# Light_Module.net
KiCad netlist of a schematic drawn in EAGLE
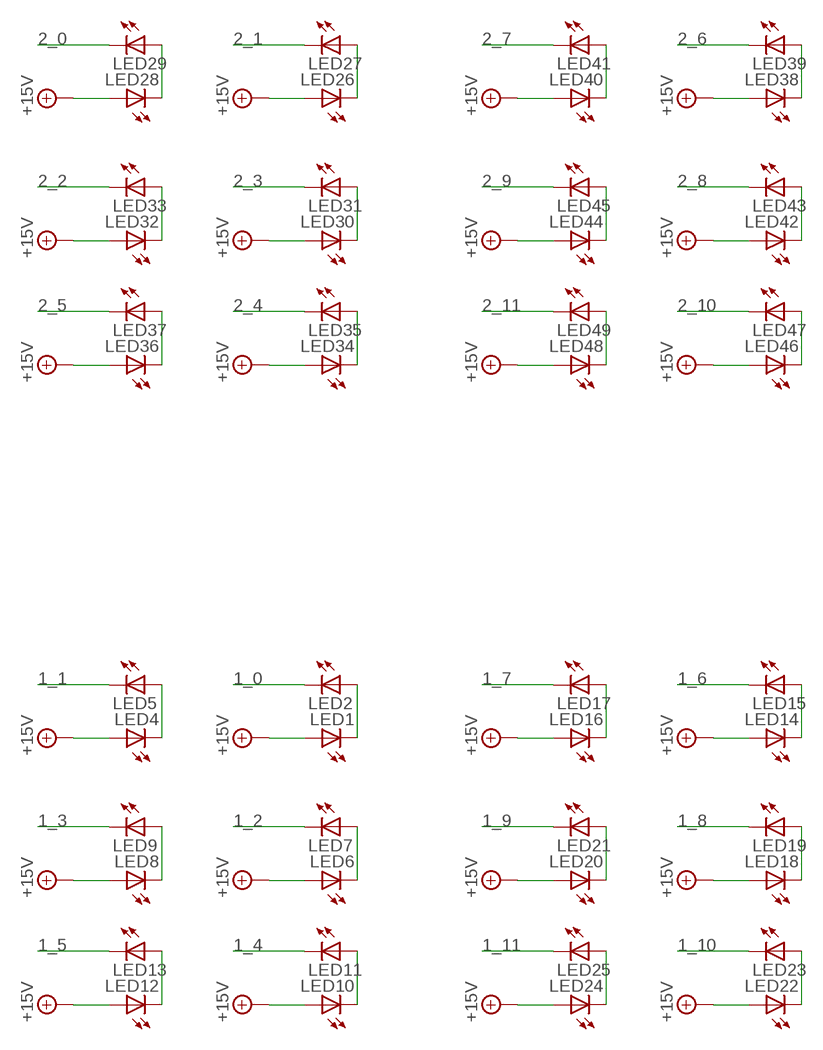
[diagram p0: schematic, sheet 1]
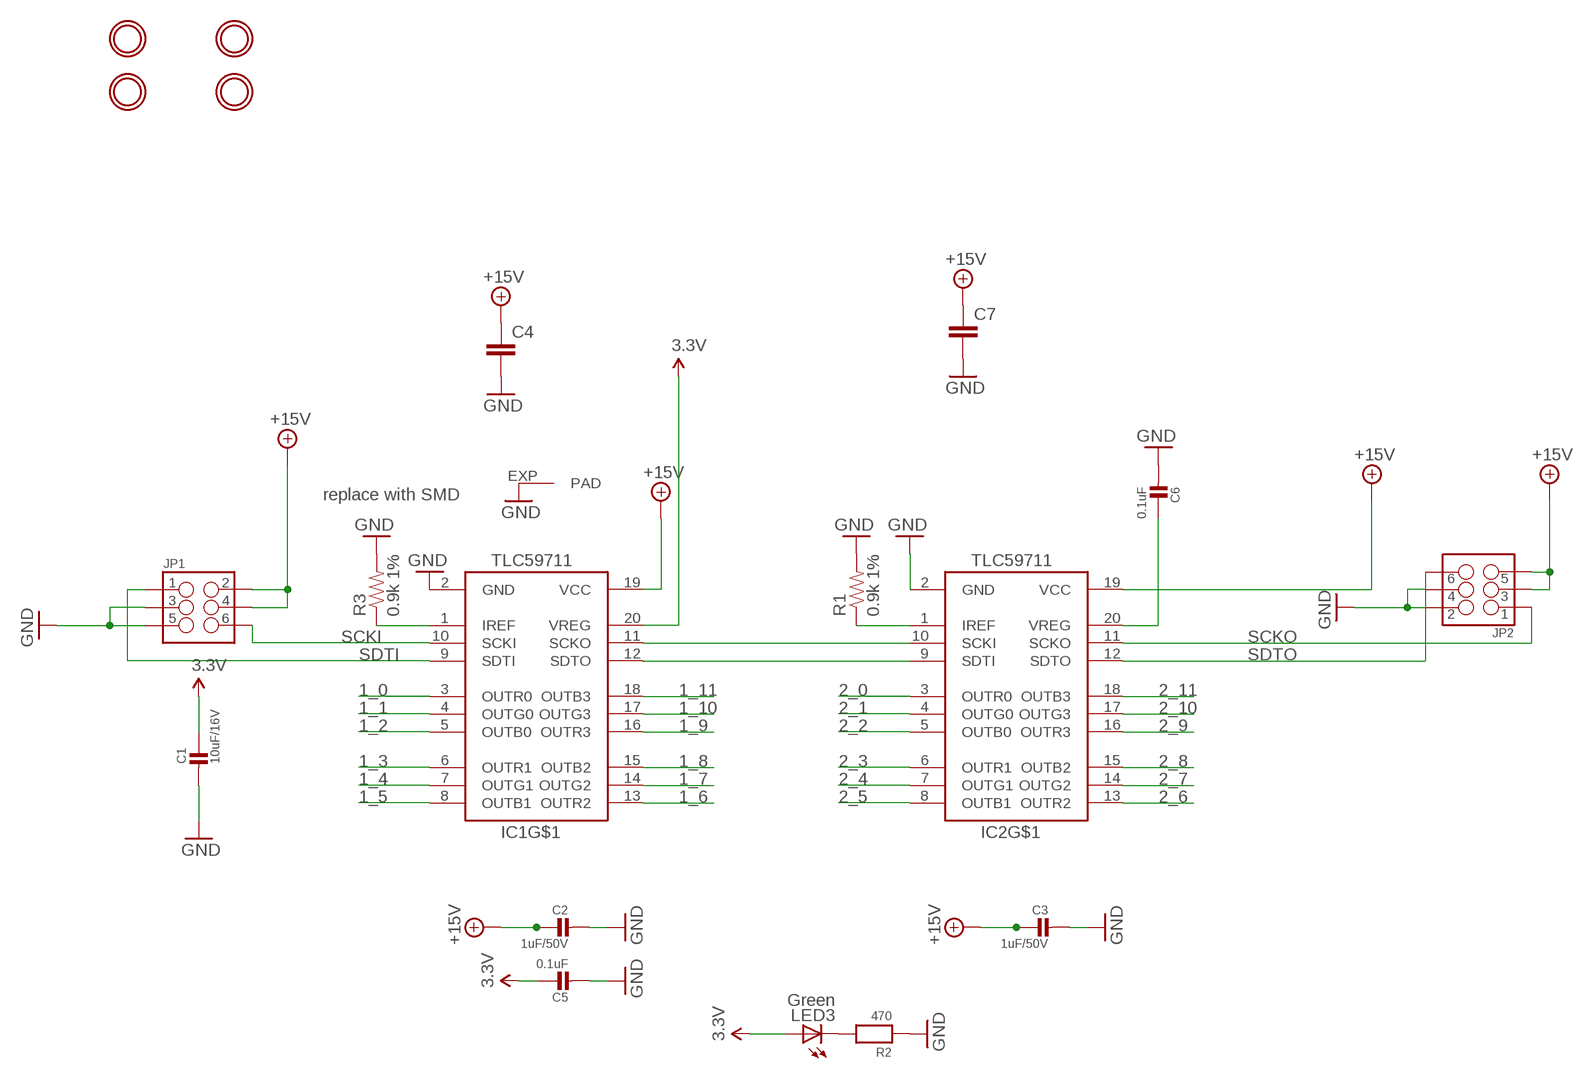
[diagram p1: schematic, sheet 2]

(export (version "E")
  (design (tool "Eeschema 10.0.6"))
  (components
    (comp (ref "LED1")
      (value "LED")
      (footprint "eagle-import:DS205")
      (libsource (lib "eagle-import") (part "digikey_LED"))
    )
    (comp (ref "LED2")
      (value "LED")
      (footprint "eagle-import:DS205")
      (libsource (lib "eagle-import") (part "digikey_LED"))
    )
    (comp (ref "LED4")
      (value "LED")
      (footprint "eagle-import:DS205")
      (libsource (lib "eagle-import") (part "digikey_LED"))
    )
    (comp (ref "LED5")
      (value "LED")
      (footprint "eagle-import:DS205")
      (libsource (lib "eagle-import") (part "digikey_LED"))
    )
    (comp (ref "LED6")
      (value "LED")
      (footprint "eagle-import:DS205")
      (libsource (lib "eagle-import") (part "digikey_LED"))
    )
    (comp (ref "LED7")
      (value "LED")
      (footprint "eagle-import:DS205")
      (libsource (lib "eagle-import") (part "digikey_LED"))
    )
    (comp (ref "LED8")
      (value "LED")
      (footprint "eagle-import:DS205")
      (libsource (lib "eagle-import") (part "digikey_LED"))
    )
    (comp (ref "LED9")
      (value "LED")
      (footprint "eagle-import:DS205")
      (libsource (lib "eagle-import") (part "digikey_LED"))
    )
    (comp (ref "LED10")
      (value "LED")
      (footprint "eagle-import:DS205")
      (libsource (lib "eagle-import") (part "digikey_LED"))
    )
    (comp (ref "LED11")
      (value "LED")
      (footprint "eagle-import:DS205")
      (libsource (lib "eagle-import") (part "digikey_LED"))
    )
    (comp (ref "LED12")
      (value "LED")
      (footprint "eagle-import:DS205")
      (libsource (lib "eagle-import") (part "digikey_LED"))
    )
    (comp (ref "LED13")
      (value "LED")
      (footprint "eagle-import:DS205")
      (libsource (lib "eagle-import") (part "digikey_LED"))
    )
    (comp (ref "LED14")
      (value "LED")
      (footprint "eagle-import:DS205")
      (libsource (lib "eagle-import") (part "digikey_LED"))
    )
    (comp (ref "LED15")
      (value "LED")
      (footprint "eagle-import:DS205")
      (libsource (lib "eagle-import") (part "digikey_LED"))
    )
    (comp (ref "LED16")
      (value "LED")
      (footprint "eagle-import:DS205")
      (libsource (lib "eagle-import") (part "digikey_LED"))
    )
    (comp (ref "LED17")
      (value "LED")
      (footprint "eagle-import:DS205")
      (libsource (lib "eagle-import") (part "digikey_LED"))
    )
    (comp (ref "LED18")
      (value "LED")
      (footprint "eagle-import:DS205")
      (libsource (lib "eagle-import") (part "digikey_LED"))
    )
    (comp (ref "LED19")
      (value "LED")
      (footprint "eagle-import:DS205")
      (libsource (lib "eagle-import") (part "digikey_LED"))
    )
    (comp (ref "LED20")
      (value "LED")
      (footprint "eagle-import:DS205")
      (libsource (lib "eagle-import") (part "digikey_LED"))
    )
    (comp (ref "LED21")
      (value "LED")
      (footprint "eagle-import:DS205")
      (libsource (lib "eagle-import") (part "digikey_LED"))
    )
    (comp (ref "LED22")
      (value "LED")
      (footprint "eagle-import:DS205")
      (libsource (lib "eagle-import") (part "digikey_LED"))
    )
    (comp (ref "LED23")
      (value "LED")
      (footprint "eagle-import:DS205")
      (libsource (lib "eagle-import") (part "digikey_LED"))
    )
    (comp (ref "LED24")
      (value "LED")
      (footprint "eagle-import:DS205")
      (libsource (lib "eagle-import") (part "digikey_LED"))
    )
    (comp (ref "LED25")
      (value "LED")
      (footprint "eagle-import:DS205")
      (libsource (lib "eagle-import") (part "digikey_LED"))
    )
    (comp (ref "LED26")
      (value "LED")
      (footprint "eagle-import:DS205")
      (libsource (lib "eagle-import") (part "digikey_LED"))
    )
    (comp (ref "LED27")
      (value "LED")
      (footprint "eagle-import:DS205")
      (libsource (lib "eagle-import") (part "digikey_LED"))
    )
    (comp (ref "LED28")
      (value "LED")
      (footprint "eagle-import:DS205")
      (libsource (lib "eagle-import") (part "digikey_LED"))
    )
    (comp (ref "LED29")
      (value "LED")
      (footprint "eagle-import:DS205")
      (libsource (lib "eagle-import") (part "digikey_LED"))
    )
    (comp (ref "LED30")
      (value "LED")
      (footprint "eagle-import:DS205")
      (libsource (lib "eagle-import") (part "digikey_LED"))
    )
    (comp (ref "LED31")
      (value "LED")
      (footprint "eagle-import:DS205")
      (libsource (lib "eagle-import") (part "digikey_LED"))
    )
    (comp (ref "LED32")
      (value "LED")
      (footprint "eagle-import:DS205")
      (libsource (lib "eagle-import") (part "digikey_LED"))
    )
    (comp (ref "LED33")
      (value "LED")
      (footprint "eagle-import:DS205")
      (libsource (lib "eagle-import") (part "digikey_LED"))
    )
    (comp (ref "LED34")
      (value "LED")
      (footprint "eagle-import:DS205")
      (libsource (lib "eagle-import") (part "digikey_LED"))
    )
    (comp (ref "LED35")
      (value "LED")
      (footprint "eagle-import:DS205")
      (libsource (lib "eagle-import") (part "digikey_LED"))
    )
    (comp (ref "LED36")
      (value "LED")
      (footprint "eagle-import:DS205")
      (libsource (lib "eagle-import") (part "digikey_LED"))
    )
    (comp (ref "LED37")
      (value "LED")
      (footprint "eagle-import:DS205")
      (libsource (lib "eagle-import") (part "digikey_LED"))
    )
    (comp (ref "LED38")
      (value "LED")
      (footprint "eagle-import:DS205")
      (libsource (lib "eagle-import") (part "digikey_LED"))
    )
    (comp (ref "LED39")
      (value "LED")
      (footprint "eagle-import:DS205")
      (libsource (lib "eagle-import") (part "digikey_LED"))
    )
    (comp (ref "LED40")
      (value "LED")
      (footprint "eagle-import:DS205")
      (libsource (lib "eagle-import") (part "digikey_LED"))
    )
    (comp (ref "LED41")
      (value "LED")
      (footprint "eagle-import:DS205")
      (libsource (lib "eagle-import") (part "digikey_LED"))
    )
    (comp (ref "LED42")
      (value "LED")
      (footprint "eagle-import:DS205")
      (libsource (lib "eagle-import") (part "digikey_LED"))
    )
    (comp (ref "LED43")
      (value "LED")
      (footprint "eagle-import:DS205")
      (libsource (lib "eagle-import") (part "digikey_LED"))
    )
    (comp (ref "LED44")
      (value "LED")
      (footprint "eagle-import:DS205")
      (libsource (lib "eagle-import") (part "digikey_LED"))
    )
    (comp (ref "LED45")
      (value "LED")
      (footprint "eagle-import:DS205")
      (libsource (lib "eagle-import") (part "digikey_LED"))
    )
    (comp (ref "LED46")
      (value "LED")
      (footprint "eagle-import:DS205")
      (libsource (lib "eagle-import") (part "digikey_LED"))
    )
    (comp (ref "LED47")
      (value "LED")
      (footprint "eagle-import:DS205")
      (libsource (lib "eagle-import") (part "digikey_LED"))
    )
    (comp (ref "LED48")
      (value "LED")
      (footprint "eagle-import:DS205")
      (libsource (lib "eagle-import") (part "digikey_LED"))
    )
    (comp (ref "LED49")
      (value "LED")
      (footprint "eagle-import:DS205")
      (libsource (lib "eagle-import") (part "digikey_LED"))
    )
    (comp (ref "C1")
      (value "10uF/16V")
      (footprint "eagle-import:0805")
      (libsource (lib "eagle-import") (part "CAP_CERAMIC0805"))
    )
    (comp (ref "C2")
      (value "1uF/50V")
      (footprint "eagle-import:0805")
      (libsource (lib "eagle-import") (part "CAP_CERAMIC0805"))
    )
    (comp (ref "C3")
      (value "1uF/50V")
      (footprint "eagle-import:0805")
      (libsource (lib "eagle-import") (part "CAP_CERAMIC0805"))
    )
    (comp (ref "C4")
      (value "CAP1206")
      (footprint "eagle-import:1206")
      (libsource (lib "eagle-import") (part "CAP1206"))
    )
    (comp (ref "C5")
      (value "0.1uF")
      (footprint "eagle-import:0805")
      (libsource (lib "eagle-import") (part "CAP_CERAMIC0805"))
    )
    (comp (ref "C6")
      (value "0.1uF")
      (footprint "eagle-import:0805")
      (libsource (lib "eagle-import") (part "CAP_CERAMIC0805"))
    )
    (comp (ref "C7")
      (value "CAP_")
      (footprint "eagle-import:AXIAL-5MM")
      (libsource (lib "eagle-import") (part "CAP_"))
    )
    (comp (ref "IC1")
      (value "TLC59711")
      (footprint "eagle-import:HTSSOP20DAP")
      (libsource (lib "eagle-import") (part "TLC59711"))
    )
    (comp (ref "IC2")
      (value "TLC59711")
      (footprint "eagle-import:HTSSOP20DAP")
      (libsource (lib "eagle-import") (part "TLC59711"))
    )
    (comp (ref "JP1")
      (value "M03X2FEMALE_SMD")
      (footprint "eagle-import:2X3_SMD")
      (libsource (lib "eagle-import") (part "M03X2FEMALE_SMD"))
    )
    (comp (ref "JP2")
      (value "M03X2FEMALE_SMD")
      (footprint "eagle-import:2X3_SMD")
      (libsource (lib "eagle-import") (part "M03X2FEMALE_SMD"))
    )
    (comp (ref "LED3")
      (value "Green")
      (footprint "eagle-import:CHIP-LED0805")
      (libsource (lib "eagle-import") (part "LEDCHIP-LED0805"))
    )
    (comp (ref "R1")
      (value "0.9k 1%")
      (footprint "eagle-import:1206")
      (libsource (lib "eagle-import") (part "RESISTOR1206"))
    )
    (comp (ref "R2")
      (value "470")
      (footprint "eagle-import:0805")
      (libsource (lib "eagle-import") (part "RESISTOR0805"))
    )
    (comp (ref "R3")
      (value "0.9k 1%")
      (footprint "eagle-import:1206")
      (libsource (lib "eagle-import") (part "RESISTOR1206"))
    )
    (comp (ref "U$1")
      (value "MOUNTINGHOLE2.5")
      (footprint "eagle-import:MOUNTINGHOLE_2.5_PLATED")
      (libsource (lib "eagle-import") (part "MOUNTINGHOLE2.5"))
    )
    (comp (ref "U$2")
      (value "MOUNTINGHOLE2.5")
      (footprint "eagle-import:MOUNTINGHOLE_2.5_PLATED")
      (libsource (lib "eagle-import") (part "MOUNTINGHOLE2.5"))
    )
    (comp (ref "U$3")
      (value "MOUNTINGHOLE2.5")
      (footprint "eagle-import:MOUNTINGHOLE_2.5_PLATED")
      (libsource (lib "eagle-import") (part "MOUNTINGHOLE2.5"))
    )
    (comp (ref "U$4")
      (value "MOUNTINGHOLE2.5")
      (footprint "eagle-import:MOUNTINGHOLE_2.5_PLATED")
      (libsource (lib "eagle-import") (part "MOUNTINGHOLE2.5"))
    )
  )
  (nets
    (net (code "1") (name "+15V") (class "Default")
      (node (ref "C2") (pin "1") (pinfunction "P$1_1") (pintype "passive"))
      (node (ref "C3") (pin "1") (pinfunction "P$1_1") (pintype "passive"))
      (node (ref "C4") (pin "1") (pinfunction "1_1") (pintype "passive"))
      (node (ref "C7") (pin "P$1") (pinfunction "1_P$1") (pintype "passive"))
      (node (ref "IC1") (pin "19") (pinfunction "VCC_19") (pintype "power_in"))
      (node (ref "IC2") (pin "19") (pinfunction "VCC_19") (pintype "power_in"))
      (node (ref "JP1") (pin "2") (pinfunction "2_2") (pintype "bidirectional"))
      (node (ref "JP1") (pin "4") (pinfunction "4_4") (pintype "bidirectional"))
      (node (ref "JP2") (pin "3") (pinfunction "3_3") (pintype "bidirectional"))
      (node (ref "JP2") (pin "5") (pinfunction "5_5") (pintype "bidirectional"))
      (node (ref "LED1") (pin "P$1") (pinfunction "A_P$1") (pintype "passive"))
      (node (ref "LED10") (pin "P$1") (pinfunction "A_P$1") (pintype "passive"))
      (node (ref "LED12") (pin "P$1") (pinfunction "A_P$1") (pintype "passive"))
      (node (ref "LED14") (pin "P$1") (pinfunction "A_P$1") (pintype "passive"))
      (node (ref "LED16") (pin "P$1") (pinfunction "A_P$1") (pintype "passive"))
      (node (ref "LED18") (pin "P$1") (pinfunction "A_P$1") (pintype "passive"))
      (node (ref "LED20") (pin "P$1") (pinfunction "A_P$1") (pintype "passive"))
      (node (ref "LED22") (pin "P$1") (pinfunction "A_P$1") (pintype "passive"))
      (node (ref "LED24") (pin "P$1") (pinfunction "A_P$1") (pintype "passive"))
      (node (ref "LED26") (pin "P$1") (pinfunction "A_P$1") (pintype "passive"))
      (node (ref "LED28") (pin "P$1") (pinfunction "A_P$1") (pintype "passive"))
      (node (ref "LED30") (pin "P$1") (pinfunction "A_P$1") (pintype "passive"))
      (node (ref "LED32") (pin "P$1") (pinfunction "A_P$1") (pintype "passive"))
      (node (ref "LED34") (pin "P$1") (pinfunction "A_P$1") (pintype "passive"))
      (node (ref "LED36") (pin "P$1") (pinfunction "A_P$1") (pintype "passive"))
      (node (ref "LED38") (pin "P$1") (pinfunction "A_P$1") (pintype "passive"))
      (node (ref "LED4") (pin "P$1") (pinfunction "A_P$1") (pintype "passive"))
      (node (ref "LED40") (pin "P$1") (pinfunction "A_P$1") (pintype "passive"))
      (node (ref "LED42") (pin "P$1") (pinfunction "A_P$1") (pintype "passive"))
      (node (ref "LED44") (pin "P$1") (pinfunction "A_P$1") (pintype "passive"))
      (node (ref "LED46") (pin "P$1") (pinfunction "A_P$1") (pintype "passive"))
      (node (ref "LED48") (pin "P$1") (pinfunction "A_P$1") (pintype "passive"))
      (node (ref "LED6") (pin "P$1") (pinfunction "A_P$1") (pintype "passive"))
      (node (ref "LED8") (pin "P$1") (pinfunction "A_P$1") (pintype "passive"))
    )
    (net (code "2") (name "1_0") (class "Default")
      (node (ref "IC1") (pin "3") (pinfunction "OUTR0_3") (pintype "open_collector"))
      (node (ref "LED2") (pin "P$2") (pinfunction "C_P$2") (pintype "passive"))
    )
    (net (code "3") (name "1_1") (class "Default")
      (node (ref "IC1") (pin "4") (pinfunction "OUTG0_4") (pintype "open_collector"))
      (node (ref "LED5") (pin "P$2") (pinfunction "C_P$2") (pintype "passive"))
    )
    (net (code "4") (name "1_2") (class "Default")
      (node (ref "IC1") (pin "5") (pinfunction "OUTB0_5") (pintype "open_collector"))
      (node (ref "LED7") (pin "P$2") (pinfunction "C_P$2") (pintype "passive"))
    )
    (net (code "5") (name "1_3") (class "Default")
      (node (ref "IC1") (pin "6") (pinfunction "OUTR1_6") (pintype "open_collector"))
      (node (ref "LED9") (pin "P$2") (pinfunction "C_P$2") (pintype "passive"))
    )
    (net (code "6") (name "1_4") (class "Default")
      (node (ref "IC1") (pin "7") (pinfunction "OUTG1_7") (pintype "open_collector"))
      (node (ref "LED11") (pin "P$2") (pinfunction "C_P$2") (pintype "passive"))
    )
    (net (code "7") (name "1_5") (class "Default")
      (node (ref "IC1") (pin "8") (pinfunction "OUTB1_8") (pintype "open_collector"))
      (node (ref "LED13") (pin "P$2") (pinfunction "C_P$2") (pintype "passive"))
    )
    (net (code "8") (name "1_6") (class "Default")
      (node (ref "IC1") (pin "13") (pinfunction "OUTR2_13") (pintype "open_collector"))
      (node (ref "LED15") (pin "P$2") (pinfunction "C_P$2") (pintype "passive"))
    )
    (net (code "9") (name "1_7") (class "Default")
      (node (ref "IC1") (pin "14") (pinfunction "OUTG2_14") (pintype "open_collector"))
      (node (ref "LED17") (pin "P$2") (pinfunction "C_P$2") (pintype "passive"))
    )
    (net (code "10") (name "1_8") (class "Default")
      (node (ref "IC1") (pin "15") (pinfunction "OUTB2_15") (pintype "open_collector"))
      (node (ref "LED19") (pin "P$2") (pinfunction "C_P$2") (pintype "passive"))
    )
    (net (code "11") (name "1_9") (class "Default")
      (node (ref "IC1") (pin "16") (pinfunction "OUTR3_16") (pintype "open_collector"))
      (node (ref "LED21") (pin "P$2") (pinfunction "C_P$2") (pintype "passive"))
    )
    (net (code "12") (name "1_10") (class "Default")
      (node (ref "IC1") (pin "17") (pinfunction "OUTG3_17") (pintype "open_collector"))
      (node (ref "LED23") (pin "P$2") (pinfunction "C_P$2") (pintype "passive"))
    )
    (net (code "13") (name "1_11") (class "Default")
      (node (ref "IC1") (pin "18") (pinfunction "OUTB3_18") (pintype "open_collector"))
      (node (ref "LED25") (pin "P$2") (pinfunction "C_P$2") (pintype "passive"))
    )
    (net (code "14") (name "2_0") (class "Default")
      (node (ref "IC2") (pin "3") (pinfunction "OUTR0_3") (pintype "open_collector"))
      (node (ref "LED29") (pin "P$2") (pinfunction "C_P$2") (pintype "passive"))
    )
    (net (code "15") (name "2_1") (class "Default")
      (node (ref "IC2") (pin "4") (pinfunction "OUTG0_4") (pintype "open_collector"))
      (node (ref "LED27") (pin "P$2") (pinfunction "C_P$2") (pintype "passive"))
    )
    (net (code "16") (name "2_2") (class "Default")
      (node (ref "IC2") (pin "5") (pinfunction "OUTB0_5") (pintype "open_collector"))
      (node (ref "LED33") (pin "P$2") (pinfunction "C_P$2") (pintype "passive"))
    )
    (net (code "17") (name "2_3") (class "Default")
      (node (ref "IC2") (pin "6") (pinfunction "OUTR1_6") (pintype "open_collector"))
      (node (ref "LED31") (pin "P$2") (pinfunction "C_P$2") (pintype "passive"))
    )
    (net (code "18") (name "2_4") (class "Default")
      (node (ref "IC2") (pin "7") (pinfunction "OUTG1_7") (pintype "open_collector"))
      (node (ref "LED35") (pin "P$2") (pinfunction "C_P$2") (pintype "passive"))
    )
    (net (code "19") (name "2_5") (class "Default")
      (node (ref "IC2") (pin "8") (pinfunction "OUTB1_8") (pintype "open_collector"))
      (node (ref "LED37") (pin "P$2") (pinfunction "C_P$2") (pintype "passive"))
    )
    (net (code "20") (name "2_6") (class "Default")
      (node (ref "IC2") (pin "13") (pinfunction "OUTR2_13") (pintype "open_collector"))
      (node (ref "LED39") (pin "P$2") (pinfunction "C_P$2") (pintype "passive"))
    )
    (net (code "21") (name "2_7") (class "Default")
      (node (ref "IC2") (pin "14") (pinfunction "OUTG2_14") (pintype "open_collector"))
      (node (ref "LED41") (pin "P$2") (pinfunction "C_P$2") (pintype "passive"))
    )
    (net (code "22") (name "2_8") (class "Default")
      (node (ref "IC2") (pin "15") (pinfunction "OUTB2_15") (pintype "open_collector"))
      (node (ref "LED43") (pin "P$2") (pinfunction "C_P$2") (pintype "passive"))
    )
    (net (code "23") (name "2_9") (class "Default")
      (node (ref "IC2") (pin "16") (pinfunction "OUTR3_16") (pintype "open_collector"))
      (node (ref "LED45") (pin "P$2") (pinfunction "C_P$2") (pintype "passive"))
    )
    (net (code "24") (name "2_10") (class "Default")
      (node (ref "IC2") (pin "17") (pinfunction "OUTG3_17") (pintype "open_collector"))
      (node (ref "LED47") (pin "P$2") (pinfunction "C_P$2") (pintype "passive"))
    )
    (net (code "25") (name "2_11") (class "Default")
      (node (ref "IC2") (pin "18") (pinfunction "OUTB3_18") (pintype "open_collector"))
      (node (ref "LED49") (pin "P$2") (pinfunction "C_P$2") (pintype "passive"))
    )
    (net (code "26") (name "3.3V") (class "Default")
      (node (ref "C1") (pin "1") (pinfunction "P$1_1") (pintype "passive"))
      (node (ref "C5") (pin "1") (pinfunction "P$1_1") (pintype "passive"))
      (node (ref "IC1") (pin "20") (pinfunction "VREG_20") (pintype "bidirectional"))
      (node (ref "LED3") (pin "A") (pinfunction "A_A") (pintype "passive"))
    )
    (net (code "27") (name "GND") (class "Default")
      (node (ref "C1") (pin "2") (pinfunction "P$2_2") (pintype "passive"))
      (node (ref "C2") (pin "2") (pinfunction "P$2_2") (pintype "passive"))
      (node (ref "C3") (pin "2") (pinfunction "P$2_2") (pintype "passive"))
      (node (ref "C4") (pin "2") (pinfunction "2_2") (pintype "passive"))
      (node (ref "C5") (pin "2") (pinfunction "P$2_2") (pintype "passive"))
      (node (ref "C6") (pin "2") (pinfunction "P$2_2") (pintype "passive"))
      (node (ref "C7") (pin "P$2") (pinfunction "2_P$2") (pintype "passive"))
      (node (ref "IC1") (pin "2") (pinfunction "GND_2") (pintype "power_in"))
      (node (ref "IC1") (pin "EXP") (pinfunction "PAD_EXP") (pintype "passive"))
      (node (ref "IC2") (pin "2") (pinfunction "GND_2") (pintype "power_in"))
      (node (ref "JP1") (pin "3") (pinfunction "3_3") (pintype "bidirectional"))
      (node (ref "JP1") (pin "5") (pinfunction "5_5") (pintype "bidirectional"))
      (node (ref "JP2") (pin "2") (pinfunction "2_2") (pintype "bidirectional"))
      (node (ref "JP2") (pin "4") (pinfunction "4_4") (pintype "bidirectional"))
      (node (ref "R1") (pin "2") (pinfunction "2_2") (pintype "passive"))
      (node (ref "R2") (pin "1") (pinfunction "1_1") (pintype "passive"))
      (node (ref "R3") (pin "2") (pinfunction "2_2") (pintype "passive"))
    )
    (net (code "28") (name "Net-(C6-P$1)") (class "Default")
      (node (ref "C6") (pin "1") (pinfunction "P$1_1") (pintype "passive"))
      (node (ref "IC2") (pin "20") (pinfunction "VREG_20") (pintype "bidirectional"))
    )
    (net (code "29") (name "Net-(IC1A-IREF)") (class "Default")
      (node (ref "IC1") (pin "1") (pinfunction "IREF_1") (pintype "bidirectional"))
      (node (ref "R3") (pin "1") (pinfunction "1_1") (pintype "passive"))
    )
    (net (code "30") (name "Net-(IC1A-SCKO)") (class "Default")
      (node (ref "IC1") (pin "11") (pinfunction "SCKO_11") (pintype "output"))
      (node (ref "IC2") (pin "10") (pinfunction "SCKI_10") (pintype "input"))
    )
    (net (code "31") (name "Net-(IC1A-SDTO)") (class "Default")
      (node (ref "IC1") (pin "12") (pinfunction "SDTO_12") (pintype "output"))
      (node (ref "IC2") (pin "9") (pinfunction "SDTI_9") (pintype "input"))
    )
    (net (code "32") (name "Net-(IC2A-IREF)") (class "Default")
      (node (ref "IC2") (pin "1") (pinfunction "IREF_1") (pintype "bidirectional"))
      (node (ref "R1") (pin "1") (pinfunction "1_1") (pintype "passive"))
    )
    (net (code "33") (name "Net-(LED1-C)") (class "Default")
      (node (ref "LED1") (pin "P$2") (pinfunction "C_P$2") (pintype "passive"))
      (node (ref "LED2") (pin "P$1") (pinfunction "A_P$1") (pintype "passive"))
    )
    (net (code "34") (name "Net-(LED3-PadC)") (class "Default")
      (node (ref "LED3") (pin "C") (pinfunction "C_C") (pintype "passive"))
      (node (ref "R2") (pin "2") (pinfunction "2_2") (pintype "passive"))
    )
    (net (code "35") (name "Net-(LED4-C)") (class "Default")
      (node (ref "LED4") (pin "P$2") (pinfunction "C_P$2") (pintype "passive"))
      (node (ref "LED5") (pin "P$1") (pinfunction "A_P$1") (pintype "passive"))
    )
    (net (code "36") (name "Net-(LED6-C)") (class "Default")
      (node (ref "LED6") (pin "P$2") (pinfunction "C_P$2") (pintype "passive"))
      (node (ref "LED7") (pin "P$1") (pinfunction "A_P$1") (pintype "passive"))
    )
    (net (code "37") (name "Net-(LED8-C)") (class "Default")
      (node (ref "LED8") (pin "P$2") (pinfunction "C_P$2") (pintype "passive"))
      (node (ref "LED9") (pin "P$1") (pinfunction "A_P$1") (pintype "passive"))
    )
    (net (code "38") (name "Net-(LED10-C)") (class "Default")
      (node (ref "LED10") (pin "P$2") (pinfunction "C_P$2") (pintype "passive"))
      (node (ref "LED11") (pin "P$1") (pinfunction "A_P$1") (pintype "passive"))
    )
    (net (code "39") (name "Net-(LED12-C)") (class "Default")
      (node (ref "LED12") (pin "P$2") (pinfunction "C_P$2") (pintype "passive"))
      (node (ref "LED13") (pin "P$1") (pinfunction "A_P$1") (pintype "passive"))
    )
    (net (code "40") (name "Net-(LED14-C)") (class "Default")
      (node (ref "LED14") (pin "P$2") (pinfunction "C_P$2") (pintype "passive"))
      (node (ref "LED15") (pin "P$1") (pinfunction "A_P$1") (pintype "passive"))
    )
    (net (code "41") (name "Net-(LED16-C)") (class "Default")
      (node (ref "LED16") (pin "P$2") (pinfunction "C_P$2") (pintype "passive"))
      (node (ref "LED17") (pin "P$1") (pinfunction "A_P$1") (pintype "passive"))
    )
    (net (code "42") (name "Net-(LED18-C)") (class "Default")
      (node (ref "LED18") (pin "P$2") (pinfunction "C_P$2") (pintype "passive"))
      (node (ref "LED19") (pin "P$1") (pinfunction "A_P$1") (pintype "passive"))
    )
    (net (code "43") (name "Net-(LED20-C)") (class "Default")
      (node (ref "LED20") (pin "P$2") (pinfunction "C_P$2") (pintype "passive"))
      (node (ref "LED21") (pin "P$1") (pinfunction "A_P$1") (pintype "passive"))
    )
    (net (code "44") (name "Net-(LED22-C)") (class "Default")
      (node (ref "LED22") (pin "P$2") (pinfunction "C_P$2") (pintype "passive"))
      (node (ref "LED23") (pin "P$1") (pinfunction "A_P$1") (pintype "passive"))
    )
    (net (code "45") (name "Net-(LED24-C)") (class "Default")
      (node (ref "LED24") (pin "P$2") (pinfunction "C_P$2") (pintype "passive"))
      (node (ref "LED25") (pin "P$1") (pinfunction "A_P$1") (pintype "passive"))
    )
    (net (code "46") (name "Net-(LED26-C)") (class "Default")
      (node (ref "LED26") (pin "P$2") (pinfunction "C_P$2") (pintype "passive"))
      (node (ref "LED27") (pin "P$1") (pinfunction "A_P$1") (pintype "passive"))
    )
    (net (code "47") (name "Net-(LED28-C)") (class "Default")
      (node (ref "LED28") (pin "P$2") (pinfunction "C_P$2") (pintype "passive"))
      (node (ref "LED29") (pin "P$1") (pinfunction "A_P$1") (pintype "passive"))
    )
    (net (code "48") (name "Net-(LED30-C)") (class "Default")
      (node (ref "LED30") (pin "P$2") (pinfunction "C_P$2") (pintype "passive"))
      (node (ref "LED31") (pin "P$1") (pinfunction "A_P$1") (pintype "passive"))
    )
    (net (code "49") (name "Net-(LED32-C)") (class "Default")
      (node (ref "LED32") (pin "P$2") (pinfunction "C_P$2") (pintype "passive"))
      (node (ref "LED33") (pin "P$1") (pinfunction "A_P$1") (pintype "passive"))
    )
    (net (code "50") (name "Net-(LED34-C)") (class "Default")
      (node (ref "LED34") (pin "P$2") (pinfunction "C_P$2") (pintype "passive"))
      (node (ref "LED35") (pin "P$1") (pinfunction "A_P$1") (pintype "passive"))
    )
    (net (code "51") (name "Net-(LED36-C)") (class "Default")
      (node (ref "LED36") (pin "P$2") (pinfunction "C_P$2") (pintype "passive"))
      (node (ref "LED37") (pin "P$1") (pinfunction "A_P$1") (pintype "passive"))
    )
    (net (code "52") (name "Net-(LED38-C)") (class "Default")
      (node (ref "LED38") (pin "P$2") (pinfunction "C_P$2") (pintype "passive"))
      (node (ref "LED39") (pin "P$1") (pinfunction "A_P$1") (pintype "passive"))
    )
    (net (code "53") (name "Net-(LED40-C)") (class "Default")
      (node (ref "LED40") (pin "P$2") (pinfunction "C_P$2") (pintype "passive"))
      (node (ref "LED41") (pin "P$1") (pinfunction "A_P$1") (pintype "passive"))
    )
    (net (code "54") (name "Net-(LED42-C)") (class "Default")
      (node (ref "LED42") (pin "P$2") (pinfunction "C_P$2") (pintype "passive"))
      (node (ref "LED43") (pin "P$1") (pinfunction "A_P$1") (pintype "passive"))
    )
    (net (code "55") (name "Net-(LED44-C)") (class "Default")
      (node (ref "LED44") (pin "P$2") (pinfunction "C_P$2") (pintype "passive"))
      (node (ref "LED45") (pin "P$1") (pinfunction "A_P$1") (pintype "passive"))
    )
    (net (code "56") (name "Net-(LED46-C)") (class "Default")
      (node (ref "LED46") (pin "P$2") (pinfunction "C_P$2") (pintype "passive"))
      (node (ref "LED47") (pin "P$1") (pinfunction "A_P$1") (pintype "passive"))
    )
    (net (code "57") (name "Net-(LED48-C)") (class "Default")
      (node (ref "LED48") (pin "P$2") (pinfunction "C_P$2") (pintype "passive"))
      (node (ref "LED49") (pin "P$1") (pinfunction "A_P$1") (pintype "passive"))
    )
    (net (code "58") (name "SCKI") (class "Default")
      (node (ref "IC1") (pin "10") (pinfunction "SCKI_10") (pintype "input"))
      (node (ref "JP1") (pin "6") (pinfunction "6_6") (pintype "bidirectional"))
    )
    (net (code "59") (name "SCKO") (class "Default")
      (node (ref "IC2") (pin "11") (pinfunction "SCKO_11") (pintype "output"))
      (node (ref "JP2") (pin "1") (pinfunction "1_1") (pintype "bidirectional"))
    )
    (net (code "60") (name "SDTI") (class "Default")
      (node (ref "IC1") (pin "9") (pinfunction "SDTI_9") (pintype "input"))
      (node (ref "JP1") (pin "1") (pinfunction "1_1") (pintype "bidirectional"))
    )
    (net (code "61") (name "SDTO") (class "Default")
      (node (ref "IC2") (pin "12") (pinfunction "SDTO_12") (pintype "output"))
      (node (ref "JP2") (pin "6") (pinfunction "6_6") (pintype "bidirectional"))
    )
  )
)
